# TinyGame_RC2.net
KiCad netlist of a schematic drawn in EAGLE
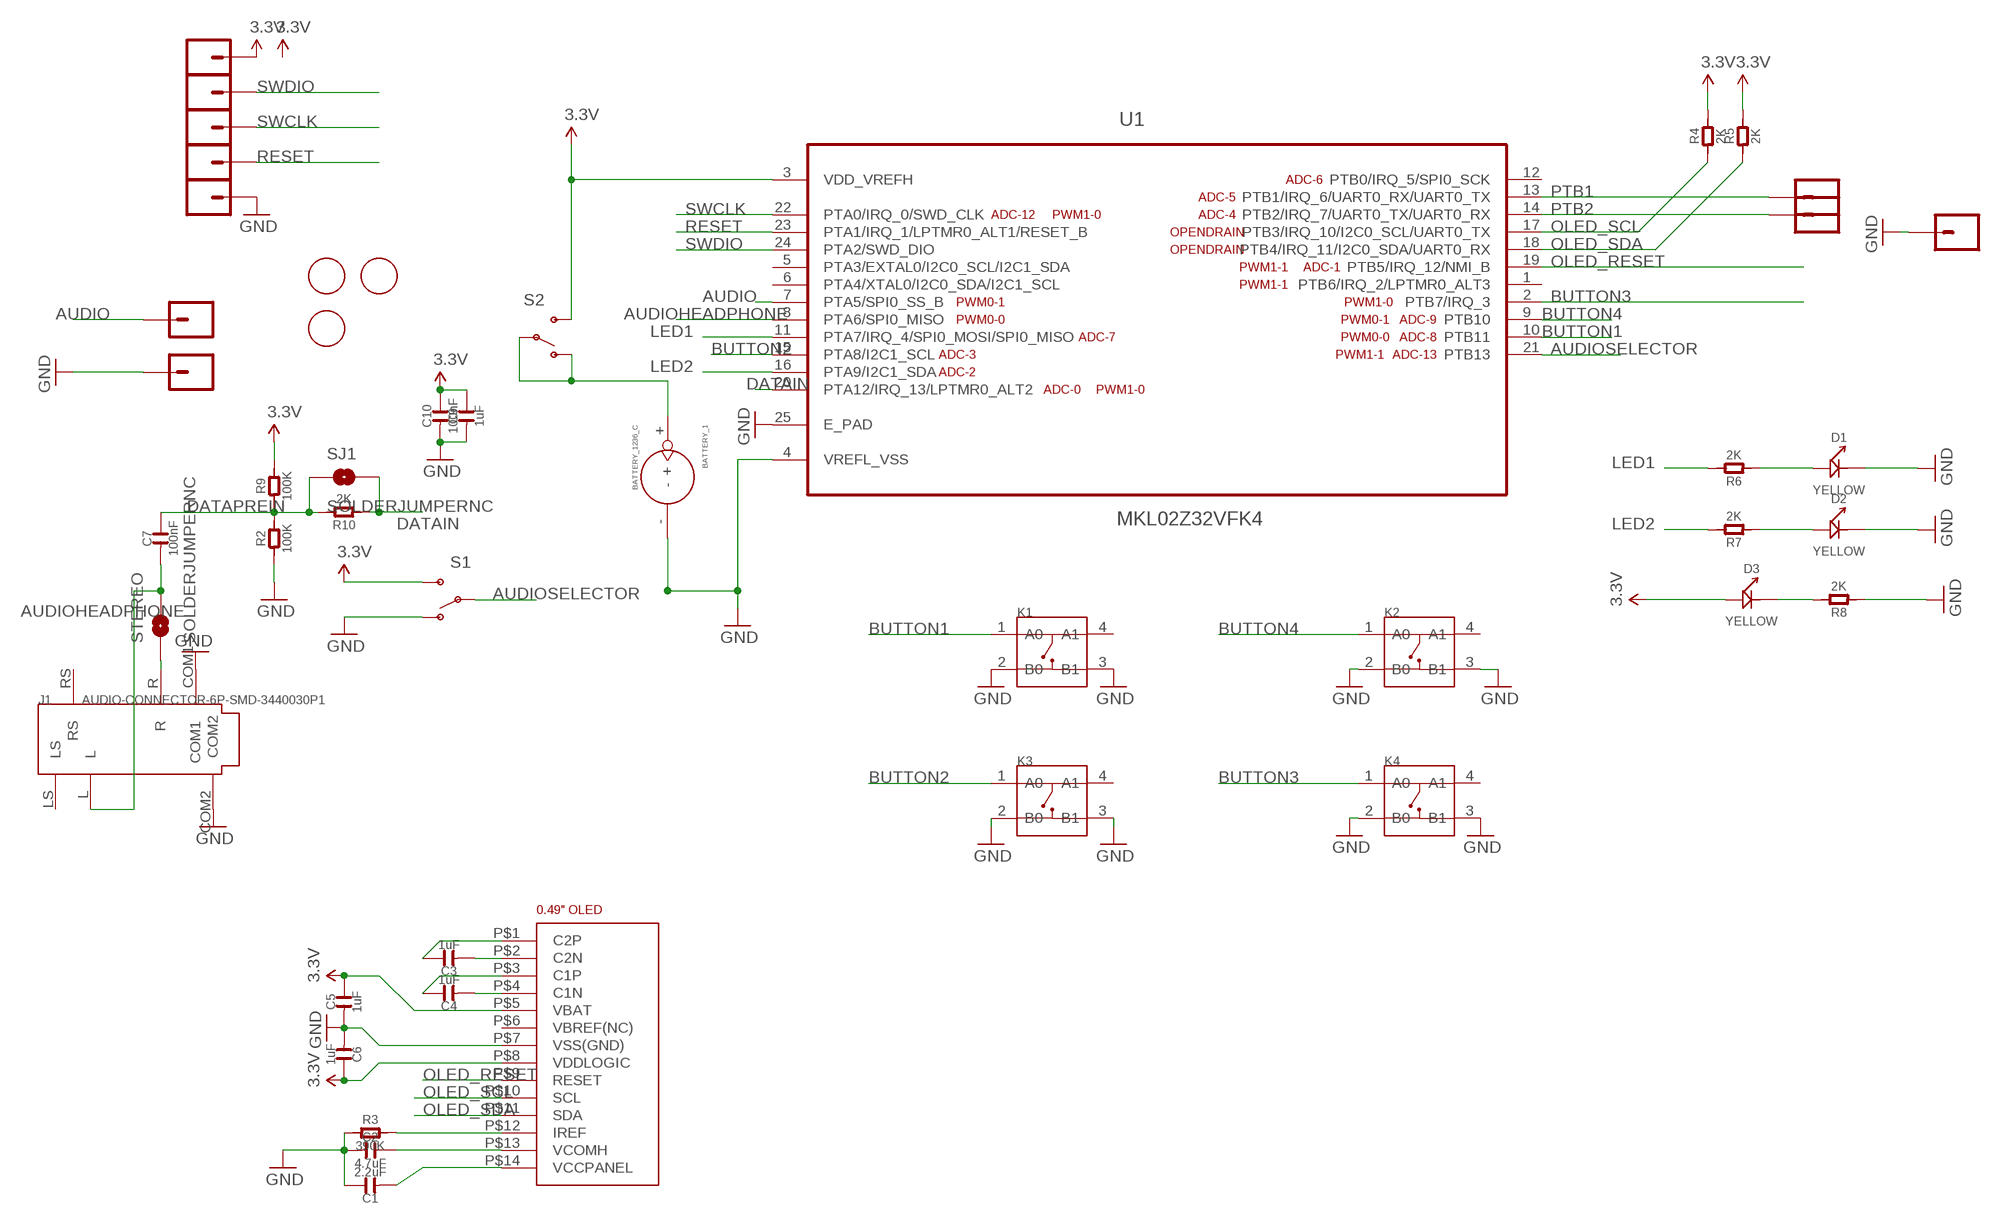
[diagram p0: schematic, sheet 1]

(export (version "E")
  (design (tool "Eeschema 10.0.6"))
  (components
    (comp (ref "AUDIOGND")
      (value "M01SMD-4.5X1.5")
      (footprint "eagle-import:PAD-1.5X4.5")
      (libsource (lib "eagle-import") (part "M01SMD-4.5X1.5"))
    )
    (comp (ref "AUDIOSIG")
      (value "M01SMD-4.5X1.5")
      (footprint "eagle-import:PAD-1.5X4.5")
      (libsource (lib "eagle-import") (part "M01SMD-4.5X1.5"))
    )
    (comp (ref "BATTERY_1")
      (value "BATTERY_1236_C")
      (footprint "eagle-import:BATTERY_1236_C")
      (libsource (lib "eagle-import") (part "BATTERY_1236_C"))
    )
    (comp (ref "C1")
      (value "2.2uF")
      (footprint "eagle-import:C0603")
      (libsource (lib "eagle-import") (part "C-0603"))
    )
    (comp (ref "C2")
      (value "4.7uF")
      (footprint "eagle-import:C0603")
      (libsource (lib "eagle-import") (part "C-0603"))
    )
    (comp (ref "C3")
      (value "1uF")
      (footprint "eagle-import:C0603")
      (libsource (lib "eagle-import") (part "C-0603"))
    )
    (comp (ref "C4")
      (value "1uF")
      (footprint "eagle-import:C0603")
      (libsource (lib "eagle-import") (part "C-0603"))
    )
    (comp (ref "C5")
      (value "1uF")
      (footprint "eagle-import:C0603")
      (libsource (lib "eagle-import") (part "C-0603"))
    )
    (comp (ref "C6")
      (value "1uF")
      (footprint "eagle-import:C0603")
      (libsource (lib "eagle-import") (part "C-0603"))
    )
    (comp (ref "C7")
      (value "100nF")
      (footprint "eagle-import:C0603")
      (libsource (lib "eagle-import") (part "C-0603"))
    )
    (comp (ref "C9")
      (value "1uF")
      (footprint "eagle-import:C0603")
      (libsource (lib "eagle-import") (part "C-0603"))
    )
    (comp (ref "C10")
      (value "100nF")
      (footprint "eagle-import:C0603")
      (libsource (lib "eagle-import") (part "C-0603"))
    )
    (comp (ref "D1")
      (value "YELLOW")
      (footprint "eagle-import:LED0603")
      (libsource (lib "eagle-import") (part "LED"))
    )
    (comp (ref "D2")
      (value "YELLOW")
      (footprint "eagle-import:LED0603")
      (libsource (lib "eagle-import") (part "LED"))
    )
    (comp (ref "D3")
      (value "YELLOW")
      (footprint "eagle-import:LED0603")
      (libsource (lib "eagle-import") (part "LED"))
    )
    (comp (ref "J1")
      (value "AUDIO-CONNECTOR-6P-SMD-3440030P1")
      (footprint "eagle-import:6P-SMD-3.5")
      (libsource (lib "eagle-import") (part "AUDIO-CONNECTOR-6P-SMD-3440030P1"))
    )
    (comp (ref "K1")
      (value "BUTTON-4P-3100010P1")
      (footprint "eagle-import:4P-SMD-6.0X6.0X5.0H")
      (libsource (lib "eagle-import") (part "BUTTON-4P-3100010P1"))
    )
    (comp (ref "K2")
      (value "BUTTON-4P-3100010P1")
      (footprint "eagle-import:4P-SMD-6.0X6.0X5.0H")
      (libsource (lib "eagle-import") (part "BUTTON-4P-3100010P1"))
    )
    (comp (ref "K3")
      (value "BUTTON-4P-3100010P1")
      (footprint "eagle-import:4P-SMD-6.0X6.0X5.0H")
      (libsource (lib "eagle-import") (part "BUTTON-4P-3100010P1"))
    )
    (comp (ref "K4")
      (value "BUTTON-4P-3100010P1")
      (footprint "eagle-import:4P-SMD-6.0X6.0X5.0H")
      (libsource (lib "eagle-import") (part "BUTTON-4P-3100010P1"))
    )
    (comp (ref "PTA6_MISO1")
      (value "M01SMD-4.5X1.5")
      (footprint "eagle-import:PAD-1.5X4.5")
      (libsource (lib "eagle-import") (part "M01SMD-4.5X1.5"))
    )
    (comp (ref "PTA6_MISO2")
      (value "M01SMD-4.5X1.5")
      (footprint "eagle-import:PAD-1.5X4.5")
      (libsource (lib "eagle-import") (part "M01SMD-4.5X1.5"))
    )
    (comp (ref "PTA6_MISO3")
      (value "M01SMD-4.5X1.5")
      (footprint "eagle-import:PAD-1.5X4.5")
      (libsource (lib "eagle-import") (part "M01SMD-4.5X1.5"))
    )
    (comp (ref "PTA6_MISO4")
      (value "M01SMD-4.5X1.5")
      (footprint "eagle-import:PAD-1.5X4.5")
      (libsource (lib "eagle-import") (part "M01SMD-4.5X1.5"))
    )
    (comp (ref "PTA6_MISO5")
      (value "M01SMD-4.5X1.5")
      (footprint "eagle-import:PAD-1.5X4.5")
      (libsource (lib "eagle-import") (part "M01SMD-4.5X1.5"))
    )
    (comp (ref "PTB1_RXTX")
      (value "M01SMD-4.5X1.5")
      (footprint "eagle-import:PAD-1.5X4.5")
      (libsource (lib "eagle-import") (part "M01SMD-4.5X1.5"))
    )
    (comp (ref "PTB2_TXRX")
      (value "M01SMD-4.5X1.5")
      (footprint "eagle-import:PAD-1.5X4.5")
      (libsource (lib "eagle-import") (part "M01SMD-4.5X1.5"))
    )
    (comp (ref "PTB2_TXRX2")
      (value "M01SMD-4.5X1.5")
      (footprint "eagle-import:PAD-1.5X4.5")
      (libsource (lib "eagle-import") (part "M01SMD-4.5X1.5"))
    )
    (comp (ref "R2")
      (value "100K")
      (footprint "eagle-import:R0603")
      (libsource (lib "eagle-import") (part "R-0603"))
    )
    (comp (ref "R3")
      (value "390K")
      (footprint "eagle-import:R0603")
      (libsource (lib "eagle-import") (part "R-0603"))
    )
    (comp (ref "R4")
      (value "2K")
      (footprint "eagle-import:R0603")
      (libsource (lib "eagle-import") (part "R-0603"))
    )
    (comp (ref "R5")
      (value "2K")
      (footprint "eagle-import:R0603")
      (libsource (lib "eagle-import") (part "R-0603"))
    )
    (comp (ref "R6")
      (value "2K")
      (footprint "eagle-import:R0603")
      (libsource (lib "eagle-import") (part "R-0603"))
    )
    (comp (ref "R7")
      (value "2K")
      (footprint "eagle-import:R0603")
      (libsource (lib "eagle-import") (part "R-0603"))
    )
    (comp (ref "R8")
      (value "2K")
      (footprint "eagle-import:R0603")
      (libsource (lib "eagle-import") (part "R-0603"))
    )
    (comp (ref "R9")
      (value "100K")
      (footprint "eagle-import:R0603")
      (libsource (lib "eagle-import") (part "R-0603"))
    )
    (comp (ref "R10")
      (value "2K")
      (footprint "eagle-import:R0603")
      (libsource (lib "eagle-import") (part "R-0603"))
    )
    (comp (ref "S1")
      (value "SWITCH-SPDT-SMD-A")
      (footprint "eagle-import:SWITCH-SPST-SMD-A")
      (libsource (lib "eagle-import") (part "SWITCH-SPDT-SMD-A"))
    )
    (comp (ref "S2")
      (value "SWITCH-SPDT-SMD-A")
      (footprint "eagle-import:SWITCH-SPST-SMD-A")
      (libsource (lib "eagle-import") (part "SWITCH-SPDT-SMD-A"))
    )
    (comp (ref "SJ1")
      (value "SOLDERJUMPERNC")
      (footprint "eagle-import:SJ_2S")
      (libsource (lib "eagle-import") (part "SOLDERJUMPERNC"))
    )
    (comp (ref "STEREO")
      (value "SOLDERJUMPERNC")
      (footprint "eagle-import:SJ_2S")
      (libsource (lib "eagle-import") (part "SOLDERJUMPERNC"))
    )
    (comp (ref "U$1")
      (value "0.49\"OLEDFOLDED")
      (footprint "eagle-import:0.49_-FPC-0.7-14-FOLDED")
      (libsource (lib "eagle-import") (part "0.49{dblquote}OLEDFOLDED"))
    )
    (comp (ref "U$2")
      (value "FIDUCIAL")
      (footprint "eagle-import:FIDUCIAL_1MM")
      (libsource (lib "eagle-import") (part "FIDUCIAL"))
    )
    (comp (ref "U$3")
      (value "FIDUCIAL")
      (footprint "eagle-import:FIDUCIAL_1MM")
      (libsource (lib "eagle-import") (part "FIDUCIAL"))
    )
    (comp (ref "U$4")
      (value "FIDUCIAL")
      (footprint "eagle-import:FIDUCIAL_1MM")
      (libsource (lib "eagle-import") (part "FIDUCIAL"))
    )
    (comp (ref "U1")
      (value "MKL02Z32VFK4")
      (footprint "eagle-import:QFN50P400X400X100-25N")
      (libsource (lib "eagle-import") (part "MKL02Z32VFK4"))
    )
  )
  (nets
    (net (code "1") (name "/AUDIO") (class "Default")
      (node (ref "AUDIOSIG") (pin "P$1") (pinfunction "1_P$1") (pintype "passive"))
      (node (ref "U1") (pin "7") (pinfunction "PTA5/SPI0_SS_B_7") (pintype "bidirectional"))
    )
    (net (code "2") (name "/AUDIOHEADPHONE") (class "Default")
      (node (ref "C7") (pin "1") (pinfunction "1_1") (pintype "bidirectional"))
      (node (ref "J1") (pin "L") (pinfunction "L_L") (pintype "bidirectional"))
      (node (ref "STEREO") (pin "2") (pinfunction "2_2") (pintype "passive"))
      (node (ref "U1") (pin "8") (pinfunction "PTA6/SPI0_MISO_8") (pintype "bidirectional"))
    )
    (net (code "3") (name "/AUDIOSELECTOR") (class "Default")
      (node (ref "S1") (pin "2") (pinfunction "P_2") (pintype "passive"))
      (node (ref "U1") (pin "21") (pinfunction "PTB13_21") (pintype "bidirectional"))
    )
    (net (code "4") (name "/BUTTON1") (class "Default")
      (node (ref "K1") (pin "1") (pinfunction "A0_1") (pintype "bidirectional"))
      (node (ref "U1") (pin "10") (pinfunction "PTB11_10") (pintype "bidirectional"))
    )
    (net (code "5") (name "/BUTTON2") (class "Default")
      (node (ref "K3") (pin "1") (pinfunction "A0_1") (pintype "bidirectional"))
      (node (ref "U1") (pin "15") (pinfunction "PTA8/I2C1_SCL_15") (pintype "bidirectional"))
    )
    (net (code "6") (name "/BUTTON3") (class "Default")
      (node (ref "K4") (pin "1") (pinfunction "A0_1") (pintype "bidirectional"))
      (node (ref "U1") (pin "2") (pinfunction "PTB7/IRQ_3_2") (pintype "bidirectional"))
    )
    (net (code "7") (name "/BUTTON4") (class "Default")
      (node (ref "K2") (pin "1") (pinfunction "A0_1") (pintype "bidirectional"))
      (node (ref "U1") (pin "9") (pinfunction "PTB10_9") (pintype "bidirectional"))
    )
    (net (code "8") (name "/DATAIN") (class "Default")
      (node (ref "R10") (pin "1") (pinfunction "1_1") (pintype "bidirectional"))
      (node (ref "SJ1") (pin "2") (pinfunction "2_2") (pintype "passive"))
      (node (ref "U1") (pin "20") (pinfunction "PTA12/IRQ_13/LPTMR0_ALT2_20") (pintype "bidirectional"))
    )
    (net (code "9") (name "/DATAPREIN") (class "Default")
      (node (ref "C7") (pin "2") (pinfunction "2_2") (pintype "bidirectional"))
      (node (ref "R10") (pin "2") (pinfunction "2_2") (pintype "bidirectional"))
      (node (ref "R2") (pin "2") (pinfunction "2_2") (pintype "bidirectional"))
      (node (ref "R9") (pin "1") (pinfunction "1_1") (pintype "bidirectional"))
      (node (ref "SJ1") (pin "1") (pinfunction "1_1") (pintype "passive"))
    )
    (net (code "10") (name "/LED1") (class "Default")
      (node (ref "R6") (pin "2") (pinfunction "2_2") (pintype "bidirectional"))
      (node (ref "U1") (pin "11") (pinfunction "PTA7/IRQ_4/SPI0_MOSI/SPI0_MISO_11") (pintype "bidirectional"))
    )
    (net (code "11") (name "/LED2") (class "Default")
      (node (ref "R7") (pin "2") (pinfunction "2_2") (pintype "bidirectional"))
      (node (ref "U1") (pin "16") (pinfunction "PTA9/I2C1_SDA_16") (pintype "bidirectional"))
    )
    (net (code "12") (name "/OLED_RESET") (class "Default")
      (node (ref "U$1") (pin "P$9") (pinfunction "RESET_P$9") (pintype "bidirectional"))
      (node (ref "U1") (pin "19") (pinfunction "PTB5/IRQ_12/NMI_B_19") (pintype "bidirectional"))
    )
    (net (code "13") (name "/OLED_SCL") (class "Default")
      (node (ref "R4") (pin "1") (pinfunction "1_1") (pintype "bidirectional"))
      (node (ref "U$1") (pin "P$10") (pinfunction "SCL_P$10") (pintype "bidirectional"))
      (node (ref "U1") (pin "17") (pinfunction "PTB3/IRQ_10/I2C0_SCL/UART0_TX_17") (pintype "bidirectional"))
    )
    (net (code "14") (name "/OLED_SDA") (class "Default")
      (node (ref "R5") (pin "1") (pinfunction "1_1") (pintype "bidirectional"))
      (node (ref "U$1") (pin "P$11") (pinfunction "SDA_P$11") (pintype "bidirectional"))
      (node (ref "U1") (pin "18") (pinfunction "PTB4/IRQ_11/I2C0_SDA/UART0_RX_18") (pintype "bidirectional"))
    )
    (net (code "15") (name "/PTB1") (class "Default")
      (node (ref "PTB1_RXTX") (pin "P$1") (pinfunction "1_P$1") (pintype "passive"))
      (node (ref "U1") (pin "13") (pinfunction "PTB1/IRQ_6/UART0_RX/UART0_TX_13") (pintype "bidirectional"))
    )
    (net (code "16") (name "/PTB2") (class "Default")
      (node (ref "PTB2_TXRX") (pin "P$1") (pinfunction "1_P$1") (pintype "passive"))
      (node (ref "U1") (pin "14") (pinfunction "PTB2/IRQ_7/UART0_TX/UART0_RX_14") (pintype "bidirectional"))
    )
    (net (code "17") (name "/RESET") (class "Default")
      (node (ref "PTA6_MISO4") (pin "P$1") (pinfunction "1_P$1") (pintype "passive"))
      (node (ref "U1") (pin "23") (pinfunction "PTA1/IRQ_1/LPTMR0_ALT1/RESET_B_23") (pintype "bidirectional"))
    )
    (net (code "18") (name "/SWCLK") (class "Default")
      (node (ref "PTA6_MISO3") (pin "P$1") (pinfunction "1_P$1") (pintype "passive"))
      (node (ref "U1") (pin "22") (pinfunction "PTA0/IRQ_0/SWD_CLK_22") (pintype "bidirectional"))
    )
    (net (code "19") (name "/SWDIO") (class "Default")
      (node (ref "PTA6_MISO2") (pin "P$1") (pinfunction "1_P$1") (pintype "passive"))
      (node (ref "U1") (pin "24") (pinfunction "PTA2/SWD_DIO_24") (pintype "bidirectional"))
    )
    (net (code "20") (name "3.3V") (class "Default")
      (node (ref "C10") (pin "2") (pinfunction "2_2") (pintype "bidirectional"))
      (node (ref "C5") (pin "2") (pinfunction "2_2") (pintype "bidirectional"))
      (node (ref "C6") (pin "2") (pinfunction "2_2") (pintype "bidirectional"))
      (node (ref "C9") (pin "2") (pinfunction "2_2") (pintype "bidirectional"))
      (node (ref "D3") (pin "+") (pinfunction "+_+") (pintype "passive"))
      (node (ref "PTA6_MISO1") (pin "P$1") (pinfunction "1_P$1") (pintype "passive"))
      (node (ref "R4") (pin "2") (pinfunction "2_2") (pintype "bidirectional"))
      (node (ref "R5") (pin "2") (pinfunction "2_2") (pintype "bidirectional"))
      (node (ref "R9") (pin "2") (pinfunction "2_2") (pintype "bidirectional"))
      (node (ref "S1") (pin "3") (pinfunction "S_3") (pintype "passive"))
      (node (ref "S2") (pin "3") (pinfunction "S_3") (pintype "passive"))
      (node (ref "U$1") (pin "P$5") (pinfunction "VBAT_P$5") (pintype "bidirectional"))
      (node (ref "U$1") (pin "P$8") (pinfunction "VDDLOGIC_P$8") (pintype "bidirectional"))
      (node (ref "U1") (pin "3") (pinfunction "VDD_VREFH_3") (pintype "power_in"))
    )
    (net (code "21") (name "GND") (class "Default")
      (node (ref "AUDIOGND") (pin "P$1") (pinfunction "1_P$1") (pintype "passive"))
      (node (ref "BATTERY_1") (pin "-") (pinfunction "-_-") (pintype "bidirectional"))
      (node (ref "C1") (pin "2") (pinfunction "2_2") (pintype "bidirectional"))
      (node (ref "C10") (pin "1") (pinfunction "1_1") (pintype "bidirectional"))
      (node (ref "C2") (pin "1") (pinfunction "1_1") (pintype "bidirectional"))
      (node (ref "C5") (pin "1") (pinfunction "1_1") (pintype "bidirectional"))
      (node (ref "C6") (pin "1") (pinfunction "1_1") (pintype "bidirectional"))
      (node (ref "C9") (pin "1") (pinfunction "1_1") (pintype "bidirectional"))
      (node (ref "D1") (pin "-") (pinfunction "-_-") (pintype "passive"))
      (node (ref "D2") (pin "-") (pinfunction "-_-") (pintype "passive"))
      (node (ref "J1") (pin "COM1") (pinfunction "COM1_COM1") (pintype "bidirectional"))
      (node (ref "J1") (pin "COM2") (pinfunction "COM2_COM2") (pintype "bidirectional"))
      (node (ref "K1") (pin "2") (pinfunction "B0_2") (pintype "bidirectional"))
      (node (ref "K1") (pin "3") (pinfunction "B1_3") (pintype "bidirectional"))
      (node (ref "K2") (pin "2") (pinfunction "B0_2") (pintype "bidirectional"))
      (node (ref "K2") (pin "3") (pinfunction "B1_3") (pintype "bidirectional"))
      (node (ref "K3") (pin "2") (pinfunction "B0_2") (pintype "bidirectional"))
      (node (ref "K3") (pin "3") (pinfunction "B1_3") (pintype "bidirectional"))
      (node (ref "K4") (pin "2") (pinfunction "B0_2") (pintype "bidirectional"))
      (node (ref "K4") (pin "3") (pinfunction "B1_3") (pintype "bidirectional"))
      (node (ref "PTA6_MISO5") (pin "P$1") (pinfunction "1_P$1") (pintype "passive"))
      (node (ref "PTB2_TXRX2") (pin "P$1") (pinfunction "1_P$1") (pintype "passive"))
      (node (ref "R2") (pin "1") (pinfunction "1_1") (pintype "bidirectional"))
      (node (ref "R3") (pin "1") (pinfunction "1_1") (pintype "bidirectional"))
      (node (ref "R8") (pin "1") (pinfunction "1_1") (pintype "bidirectional"))
      (node (ref "S1") (pin "1") (pinfunction "O_1") (pintype "passive"))
      (node (ref "U$1") (pin "P$7") (pinfunction "VSS(GND)_P$7") (pintype "bidirectional"))
      (node (ref "U1") (pin "25") (pinfunction "E_PAD_25") (pintype "passive"))
      (node (ref "U1") (pin "4") (pinfunction "VREFL_VSS_4") (pintype "passive"))
    )
    (net (code "22") (name "Net-(D1-Pad+)") (class "Default")
      (node (ref "D1") (pin "+") (pinfunction "+_+") (pintype "passive"))
      (node (ref "R6") (pin "1") (pinfunction "1_1") (pintype "bidirectional"))
    )
    (net (code "23") (name "Net-(D2-Pad+)") (class "Default")
      (node (ref "D2") (pin "+") (pinfunction "+_+") (pintype "passive"))
      (node (ref "R7") (pin "1") (pinfunction "1_1") (pintype "bidirectional"))
    )
    (net (code "24") (name "Net-(D3-Pad-)") (class "Default")
      (node (ref "D3") (pin "-") (pinfunction "-_-") (pintype "passive"))
      (node (ref "R8") (pin "2") (pinfunction "2_2") (pintype "bidirectional"))
    )
    (net (code "25") (name "Net-(J1-PadR)") (class "Default")
      (node (ref "J1") (pin "R") (pinfunction "R_R") (pintype "bidirectional"))
      (node (ref "STEREO") (pin "1") (pinfunction "1_1") (pintype "passive"))
    )
    (net (code "26") (name "Net-(S2-O)") (class "Default")
      (node (ref "BATTERY_1") (pin "+") (pinfunction "+_+") (pintype "bidirectional"))
      (node (ref "S2") (pin "1") (pinfunction "O_1") (pintype "passive"))
      (node (ref "S2") (pin "2") (pinfunction "P_2") (pintype "passive"))
    )
    (net (code "27") (name "Net-(U$1-C1N)") (class "Default")
      (node (ref "C4") (pin "1") (pinfunction "1_1") (pintype "bidirectional"))
      (node (ref "U$1") (pin "P$4") (pinfunction "C1N_P$4") (pintype "bidirectional"))
    )
    (net (code "28") (name "Net-(U$1-C1P)") (class "Default")
      (node (ref "C4") (pin "2") (pinfunction "2_2") (pintype "bidirectional"))
      (node (ref "U$1") (pin "P$3") (pinfunction "C1P_P$3") (pintype "bidirectional"))
    )
    (net (code "29") (name "Net-(U$1-C2N)") (class "Default")
      (node (ref "C3") (pin "1") (pinfunction "1_1") (pintype "bidirectional"))
      (node (ref "U$1") (pin "P$2") (pinfunction "C2N_P$2") (pintype "bidirectional"))
    )
    (net (code "30") (name "Net-(U$1-C2P)") (class "Default")
      (node (ref "C3") (pin "2") (pinfunction "2_2") (pintype "bidirectional"))
      (node (ref "U$1") (pin "P$1") (pinfunction "C2P_P$1") (pintype "bidirectional"))
    )
    (net (code "31") (name "Net-(U$1-IREF)") (class "Default")
      (node (ref "R3") (pin "2") (pinfunction "2_2") (pintype "bidirectional"))
      (node (ref "U$1") (pin "P$12") (pinfunction "IREF_P$12") (pintype "bidirectional"))
    )
    (net (code "32") (name "Net-(U$1-VCCPANEL)") (class "Default")
      (node (ref "C1") (pin "1") (pinfunction "1_1") (pintype "bidirectional"))
      (node (ref "U$1") (pin "P$14") (pinfunction "VCCPANEL_P$14") (pintype "bidirectional"))
    )
    (net (code "33") (name "Net-(U$1-VCOMH)") (class "Default")
      (node (ref "C2") (pin "2") (pinfunction "2_2") (pintype "bidirectional"))
      (node (ref "U$1") (pin "P$13") (pinfunction "VCOMH_P$13") (pintype "bidirectional"))
    )
    (net (code "34") (name "unconnected-(J1-PadLS)") (class "Default")
      (node (ref "J1") (pin "LS") (pinfunction "LS_LS") (pintype "bidirectional"))
    )
    (net (code "35") (name "unconnected-(J1-PadRS)") (class "Default")
      (node (ref "J1") (pin "RS") (pinfunction "RS_RS") (pintype "bidirectional"))
    )
    (net (code "36") (name "unconnected-(K1-A1-Pad4)") (class "Default")
      (node (ref "K1") (pin "4") (pinfunction "A1_4") (pintype "bidirectional"))
    )
    (net (code "37") (name "unconnected-(K2-A1-Pad4)") (class "Default")
      (node (ref "K2") (pin "4") (pinfunction "A1_4") (pintype "bidirectional"))
    )
    (net (code "38") (name "unconnected-(K3-A1-Pad4)") (class "Default")
      (node (ref "K3") (pin "4") (pinfunction "A1_4") (pintype "bidirectional"))
    )
    (net (code "39") (name "unconnected-(K4-A1-Pad4)") (class "Default")
      (node (ref "K4") (pin "4") (pinfunction "A1_4") (pintype "bidirectional"))
    )
    (net (code "40") (name "unconnected-(U$1-VBREF(NC)-PadP$6)") (class "Default")
      (node (ref "U$1") (pin "P$6") (pinfunction "VBREF(NC)_P$6") (pintype "bidirectional"))
    )
    (net (code "41") (name "unconnected-(U1-PTA3{slash}EXTAL0{slash}I2C0_SCL{slash}I2C1_SDA-Pad5)") (class "Default")
      (node (ref "U1") (pin "5") (pinfunction "PTA3/EXTAL0/I2C0_SCL/I2C1_SDA_5") (pintype "bidirectional"))
    )
    (net (code "42") (name "unconnected-(U1-PTA4{slash}XTAL0{slash}I2C0_SDA{slash}I2C1_SCL-Pad6)") (class "Default")
      (node (ref "U1") (pin "6") (pinfunction "PTA4/XTAL0/I2C0_SDA/I2C1_SCL_6") (pintype "bidirectional"))
    )
    (net (code "43") (name "unconnected-(U1-PTB0{slash}IRQ_5{slash}SPI0_SCK-Pad12)") (class "Default")
      (node (ref "U1") (pin "12") (pinfunction "PTB0/IRQ_5/SPI0_SCK_12") (pintype "bidirectional"))
    )
    (net (code "44") (name "unconnected-(U1-PTB6{slash}IRQ_2{slash}LPTMR0_ALT3-Pad1)") (class "Default")
      (node (ref "U1") (pin "1") (pinfunction "PTB6/IRQ_2/LPTMR0_ALT3_1") (pintype "bidirectional"))
    )
  )
)
